# AccessControl.net
KiCad netlist of a schematic drawn in EAGLE
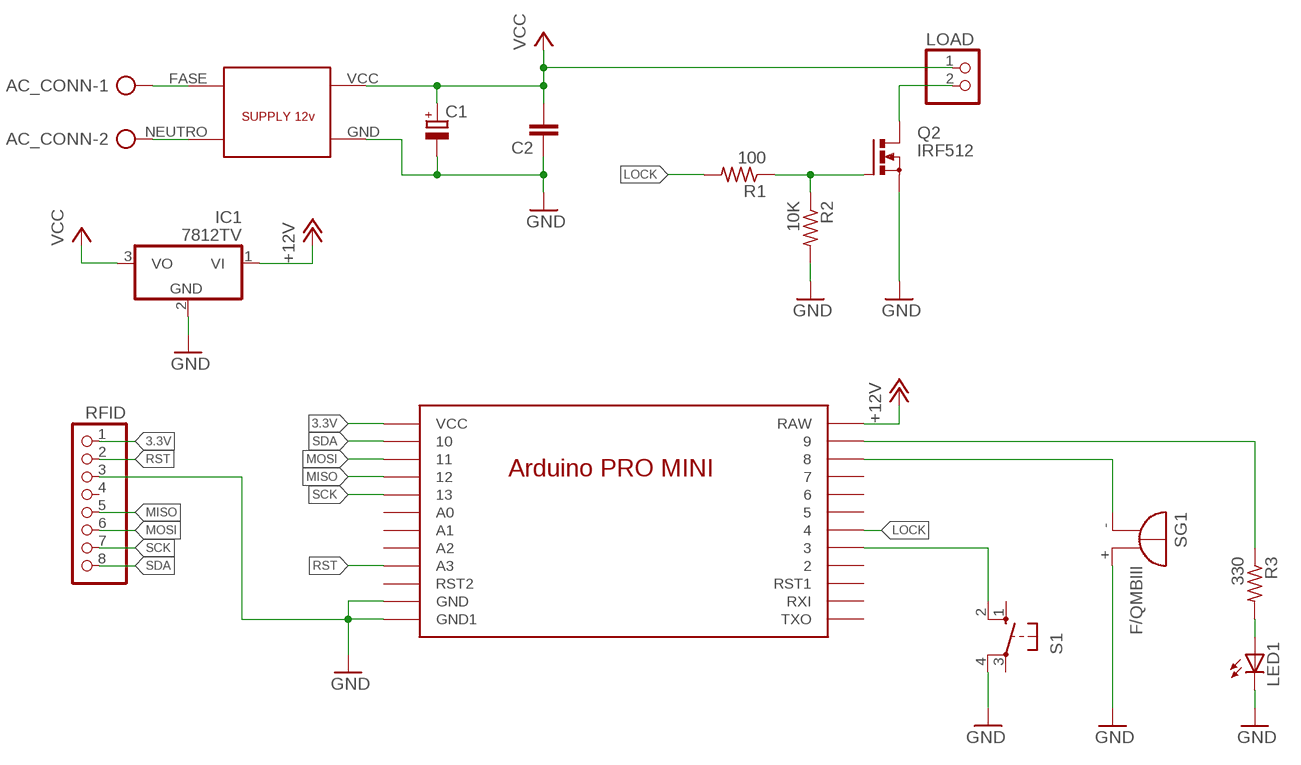
[diagram p0: schematic, sheet 1]

(export (version "E")
  (design (tool "Eeschema 10.0.6"))
  (components
    (comp (ref "AC_CONN")
      (value "AK300/2")
      (footprint "eagle-import:AK300_2")
      (libsource (lib "eagle-import") (part "AK300/2"))
    )
    (comp (ref "C1")
      (value "CPOL-EUE2.5-6")
      (footprint "eagle-import:E2,5-6")
      (libsource (lib "eagle-import") (part "CPOL-EUE2.5-6"))
    )
    (comp (ref "C2")
      (value "C2.5/2")
      (footprint "eagle-import:C2.5-2")
      (libsource (lib "eagle-import") (part "C2.5/2"))
    )
    (comp (ref "IC1")
      (value "7812TV")
      (footprint "eagle-import:TO220V")
      (libsource (lib "eagle-import") (part "78TV12"))
    )
    (comp (ref "LED1")
      (value "LED3MM")
      (footprint "eagle-import:LED3MM")
      (libsource (lib "eagle-import") (part "LED3MM"))
    )
    (comp (ref "LOAD")
      (value "PINHD-1X2")
      (footprint "eagle-import:1X02")
      (libsource (lib "eagle-import") (part "PINHD-1X2"))
    )
    (comp (ref "Q2")
      (value "IRF512")
      (footprint "eagle-import:TO220BV")
      (libsource (lib "eagle-import") (part "IRF512"))
    )
    (comp (ref "R1")
      (value "100")
      (footprint "eagle-import:0204_7")
      (libsource (lib "eagle-import") (part "R-US_0204/7"))
    )
    (comp (ref "R2")
      (value "10K")
      (footprint "eagle-import:0204_7")
      (libsource (lib "eagle-import") (part "R-US_0204/7"))
    )
    (comp (ref "R3")
      (value "330")
      (footprint "eagle-import:0204_7")
      (libsource (lib "eagle-import") (part "R-US_0204/7"))
    )
    (comp (ref "RFID")
      (value "PINHD-1X8")
      (footprint "eagle-import:1X08")
      (libsource (lib "eagle-import") (part "PINHD-1X8"))
    )
    (comp (ref "S1")
      (value "10-XX")
      (footprint "eagle-import:B3F-10XX")
      (fields (field (name "MPN") "B3F-1000"))
      (libsource (lib "eagle-import") (part "10-XX"))
    )
    (comp (ref "SG1")
      (value "F/QMBIII")
      (footprint "eagle-import:F_QMBIII")
      (libsource (lib "eagle-import") (part "F/QMBIII"))
    )
    (comp (ref "U$1")
      (value "NANO")
      (footprint "eagle-import:NANO")
      (libsource (lib "eagle-import") (part "NANO"))
    )
    (comp (ref "U$2")
      (value "SUPPLY12V")
      (footprint "eagle-import:SUPPLY12V")
      (libsource (lib "eagle-import") (part "SUPPLY12V"))
    )
  )
  (nets
    (net (code "1") (name "+12V") (class "Default")
      (node (ref "IC1") (pin "1") (pinfunction "VI_1") (pintype "input"))
      (node (ref "U$1") (pin "RAW") (pinfunction "RAW_RAW") (pintype "bidirectional"))
    )
    (net (code "2") (name "3.3V") (class "Default")
      (node (ref "RFID") (pin "1") (pinfunction "1_1") (pintype "passive"))
      (node (ref "U$1") (pin "VCC") (pinfunction "VCC_VCC") (pintype "bidirectional"))
    )
    (net (code "3") (name "GND") (class "Default")
      (node (ref "C1") (pin "-") (pinfunction "-_-") (pintype "passive"))
      (node (ref "C2") (pin "1") (pinfunction "1_1") (pintype "passive"))
      (node (ref "IC1") (pin "2") (pinfunction "GND_2") (pintype "passive"))
      (node (ref "LED1") (pin "K") (pinfunction "C_K") (pintype "passive"))
      (node (ref "Q2") (pin "S") (pinfunction "S_S") (pintype "passive"))
      (node (ref "R2") (pin "2") (pinfunction "2_2") (pintype "passive"))
      (node (ref "RFID") (pin "3") (pinfunction "3_3") (pintype "passive"))
      (node (ref "S1") (pin "4") (pinfunction "P1_4") (pintype "passive"))
      (node (ref "SG1") (pin "+") (pinfunction "-_+") (pintype "passive"))
      (node (ref "U$1") (pin "GND1") (pinfunction "GND_GND1") (pintype "bidirectional"))
      (node (ref "U$1") (pin "GND2") (pinfunction "GND1_GND2") (pintype "power_in"))
      (node (ref "U$2") (pin "GND") (pinfunction "GND_GND") (pintype "bidirectional"))
    )
    (net (code "4") (name "LOCK") (class "Default")
      (node (ref "R1") (pin "2") (pinfunction "2_2") (pintype "passive"))
      (node (ref "U$1") (pin "4") (pinfunction "4_4") (pintype "bidirectional"))
    )
    (net (code "5") (name "MISO") (class "Default")
      (node (ref "RFID") (pin "5") (pinfunction "5_5") (pintype "passive"))
      (node (ref "U$1") (pin "12") (pinfunction "12_12") (pintype "bidirectional"))
    )
    (net (code "6") (name "MOSI") (class "Default")
      (node (ref "RFID") (pin "6") (pinfunction "6_6") (pintype "passive"))
      (node (ref "U$1") (pin "11") (pinfunction "11_11") (pintype "bidirectional"))
    )
    (net (code "7") (name "Net-(AC_CONNA-KL)") (class "Default")
      (node (ref "AC_CONN") (pin "1") (pinfunction "KL_1") (pintype "passive"))
      (node (ref "U$2") (pin "FASE") (pinfunction "FASE_FASE") (pintype "bidirectional"))
    )
    (net (code "8") (name "Net-(AC_CONNB-KL)") (class "Default")
      (node (ref "AC_CONN") (pin "2") (pinfunction "KL_2") (pintype "passive"))
      (node (ref "U$2") (pin "NEUTRO") (pinfunction "NEUTRO_NEUTRO") (pintype "bidirectional"))
    )
    (net (code "9") (name "Net-(LED1-PadA)") (class "Default")
      (node (ref "LED1") (pin "A") (pinfunction "A_A") (pintype "passive"))
      (node (ref "R3") (pin "2") (pinfunction "2_2") (pintype "passive"))
    )
    (net (code "10") (name "Net-(LOAD-Pad2)") (class "Default")
      (node (ref "LOAD") (pin "2") (pinfunction "2_2") (pintype "passive"))
      (node (ref "Q2") (pin "D") (pinfunction "D_D") (pintype "passive"))
    )
    (net (code "11") (name "Net-(Q2-PadG)") (class "Default")
      (node (ref "Q2") (pin "G") (pinfunction "G_G") (pintype "passive"))
      (node (ref "R1") (pin "1") (pinfunction "1_1") (pintype "passive"))
      (node (ref "R2") (pin "1") (pinfunction "1_1") (pintype "passive"))
    )
    (net (code "12") (name "Net-(R3-Pad1)") (class "Default")
      (node (ref "R3") (pin "1") (pinfunction "1_1") (pintype "passive"))
      (node (ref "U$1") (pin "9") (pinfunction "9_9") (pintype "bidirectional"))
    )
    (net (code "13") (name "Net-(S1-S1)") (class "Default")
      (node (ref "S1") (pin "2") (pinfunction "S1_2") (pintype "passive"))
      (node (ref "U$1") (pin "3") (pinfunction "3_3") (pintype "bidirectional"))
    )
    (net (code "14") (name "Net-(SG1-+)") (class "Default")
      (node (ref "SG1") (pin "-") (pinfunction "+_-") (pintype "passive"))
      (node (ref "U$1") (pin "8") (pinfunction "8_8") (pintype "bidirectional"))
    )
    (net (code "15") (name "RST") (class "Default")
      (node (ref "RFID") (pin "2") (pinfunction "2_2") (pintype "passive"))
      (node (ref "U$1") (pin "A3") (pinfunction "A3_A3") (pintype "bidirectional"))
    )
    (net (code "16") (name "SCK") (class "Default")
      (node (ref "RFID") (pin "7") (pinfunction "7_7") (pintype "passive"))
      (node (ref "U$1") (pin "13") (pinfunction "13_13") (pintype "bidirectional"))
    )
    (net (code "17") (name "SDA") (class "Default")
      (node (ref "RFID") (pin "8") (pinfunction "8_8") (pintype "passive"))
      (node (ref "U$1") (pin "10") (pinfunction "10_10") (pintype "bidirectional"))
    )
    (net (code "18") (name "VCC") (class "Default")
      (node (ref "C1") (pin "+") (pinfunction "+_+") (pintype "passive"))
      (node (ref "C2") (pin "2") (pinfunction "2_2") (pintype "passive"))
      (node (ref "IC1") (pin "3") (pinfunction "VO_3") (pintype "passive"))
      (node (ref "LOAD") (pin "1") (pinfunction "1_1") (pintype "passive"))
      (node (ref "U$2") (pin "VCC") (pinfunction "VCC_VCC") (pintype "bidirectional"))
    )
    (net (code "19") (name "unconnected-(RFID-Pad4)") (class "Default")
      (node (ref "RFID") (pin "4") (pinfunction "4_4") (pintype "passive"))
    )
    (net (code "20") (name "unconnected-(S1-P-Pad3)") (class "Default")
      (node (ref "S1") (pin "3") (pinfunction "P_3") (pintype "passive"))
    )
    (net (code "21") (name "unconnected-(S1-S-Pad1)") (class "Default")
      (node (ref "S1") (pin "1") (pinfunction "S_1") (pintype "passive"))
    )
    (net (code "22") (name "unconnected-(U$1-Pad2)") (class "Default")
      (node (ref "U$1") (pin "2") (pinfunction "2_2") (pintype "bidirectional"))
    )
    (net (code "23") (name "unconnected-(U$1-Pad5)") (class "Default")
      (node (ref "U$1") (pin "5") (pinfunction "5_5") (pintype "bidirectional"))
    )
    (net (code "24") (name "unconnected-(U$1-Pad6)") (class "Default")
      (node (ref "U$1") (pin "6") (pinfunction "6_6") (pintype "bidirectional"))
    )
    (net (code "25") (name "unconnected-(U$1-Pad7)") (class "Default")
      (node (ref "U$1") (pin "7") (pinfunction "7_7") (pintype "bidirectional"))
    )
    (net (code "26") (name "unconnected-(U$1-PadA0)") (class "Default")
      (node (ref "U$1") (pin "A0") (pinfunction "A0_A0") (pintype "bidirectional"))
    )
    (net (code "27") (name "unconnected-(U$1-PadA1)") (class "Default")
      (node (ref "U$1") (pin "A1") (pinfunction "A1_A1") (pintype "bidirectional"))
    )
    (net (code "28") (name "unconnected-(U$1-PadA2)") (class "Default")
      (node (ref "U$1") (pin "A2") (pinfunction "A2_A2") (pintype "bidirectional"))
    )
    (net (code "29") (name "unconnected-(U$1-PadRST1)") (class "Default")
      (node (ref "U$1") (pin "RST1") (pinfunction "RST1_RST1") (pintype "bidirectional"))
    )
    (net (code "30") (name "unconnected-(U$1-PadRST2)") (class "Default")
      (node (ref "U$1") (pin "RST2") (pinfunction "RST2_RST2") (pintype "bidirectional"))
    )
    (net (code "31") (name "unconnected-(U$1-PadRXI)") (class "Default")
      (node (ref "U$1") (pin "RXI") (pinfunction "RXI_RXI") (pintype "bidirectional"))
    )
    (net (code "32") (name "unconnected-(U$1-PadTXO)") (class "Default")
      (node (ref "U$1") (pin "TXO") (pinfunction "TXO_TXO") (pintype "bidirectional"))
    )
  )
)
